# Timer_UNO.net
KiCad netlist of a schematic drawn in EAGLE
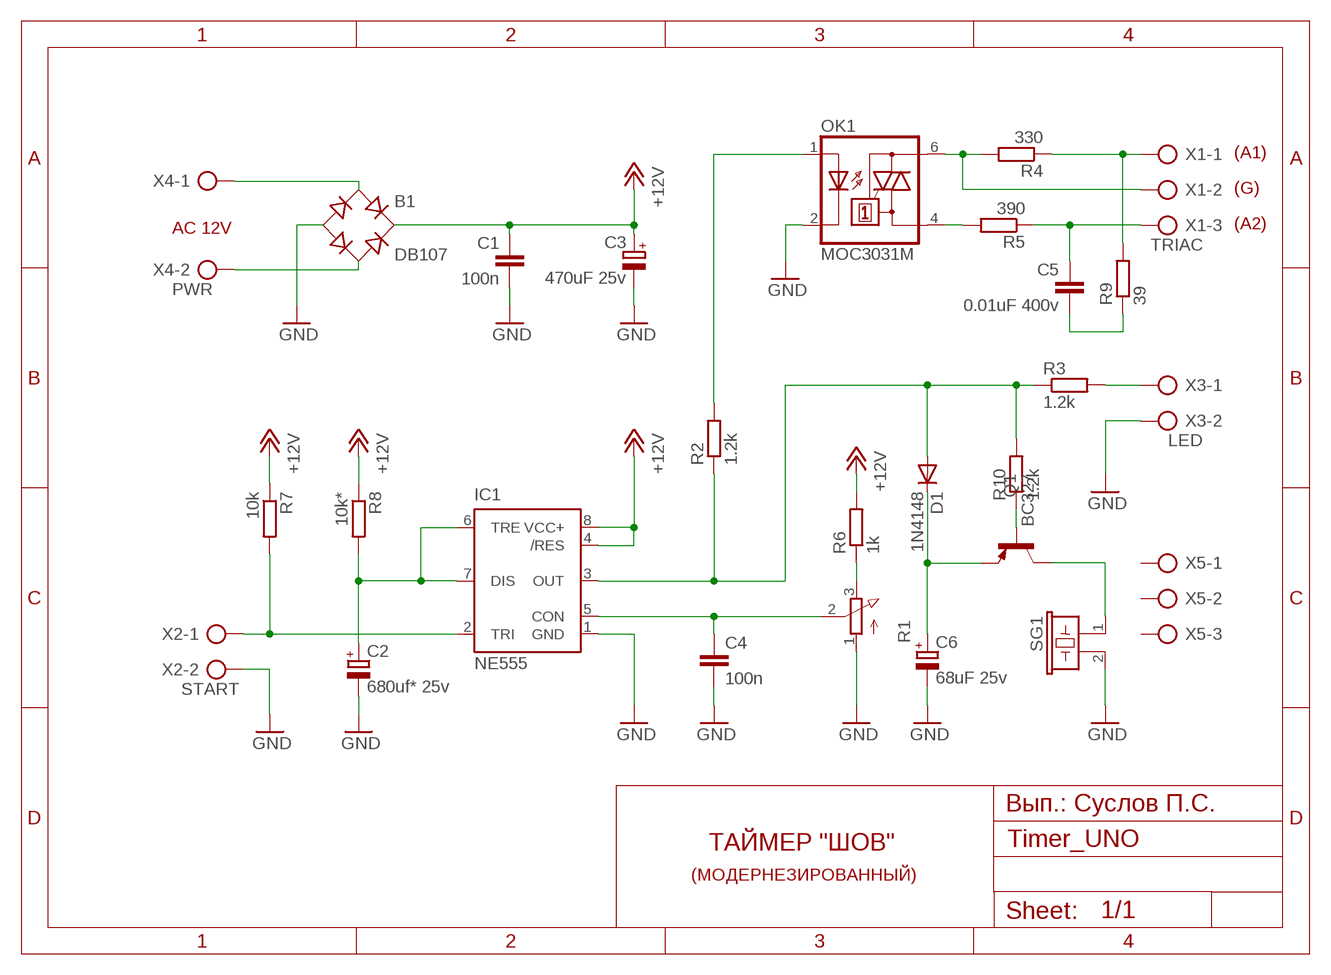
[diagram p0: schematic, sheet 1]

(export (version "E")
  (design (tool "Eeschema 10.0.6"))
  (components
    (comp (ref "B1")
      (value "DB107")
      (footprint "eagle-import:DB")
      (libsource (lib "eagle-import") (part "DB?GDB107"))
    )
    (comp (ref "C1")
      (value "100n")
      (footprint "eagle-import:C025-030X050")
      (libsource (lib "eagle-import") (part "C-EU025-030X050"))
    )
    (comp (ref "C2")
      (value "680uf* 25v")
      (footprint "eagle-import:E3,5-10")
      (libsource (lib "eagle-import") (part "CPOL-EUE3.5-10"))
    )
    (comp (ref "C3")
      (value "470uF 25v")
      (footprint "eagle-import:E3,5-8")
      (libsource (lib "eagle-import") (part "CPOL-EUE3.5-8"))
    )
    (comp (ref "C4")
      (value "100n")
      (footprint "eagle-import:C025-030X050")
      (libsource (lib "eagle-import") (part "C-EU025-030X050"))
    )
    (comp (ref "C5")
      (value "0.01uF 400v")
      (footprint "eagle-import:C075-063X106")
      (libsource (lib "eagle-import") (part "C-EU075-063X106"))
    )
    (comp (ref "C6")
      (value "68uF 25v")
      (footprint "eagle-import:E3,5-8")
      (libsource (lib "eagle-import") (part "CPOL-EUE3.5-8"))
    )
    (comp (ref "D1")
      (value "1N4148")
      (footprint "eagle-import:DO35-7")
      (libsource (lib "eagle-import") (part "1N4148DO35-7"))
    )
    (comp (ref "IC1")
      (value "NE555")
      (footprint "eagle-import:DIL-08")
      (fields (field (name "MF") "Arrow Electronics") (field (name "MPN") "NE555N"))
      (libsource (lib "eagle-import") (part "NE555"))
    )
    (comp (ref "OK1")
      (value "MOC3031M")
      (footprint "eagle-import:DIL06")
      (fields (field (name "MF") "FAIRCHILD SEMICONDUCTOR"))
      (libsource (lib "eagle-import") (part "MOC3031M"))
    )
    (comp (ref "Q1")
      (value "BC327")
      (footprint "eagle-import:TO92-EBC")
      (libsource (lib "eagle-import") (part "BC327"))
    )
    (comp (ref "R1")
      (value "3RP/1610N")
      (footprint "eagle-import:3RP_1610N")
      (libsource (lib "eagle-import") (part "3RP/1610N"))
    )
    (comp (ref "R2")
      (value "1.2k")
      (footprint "eagle-import:0207_10")
      (libsource (lib "eagle-import") (part "R-EU_0207/10"))
    )
    (comp (ref "R3")
      (value "1.2k")
      (footprint "eagle-import:0207_10")
      (libsource (lib "eagle-import") (part "R-EU_0207/10"))
    )
    (comp (ref "R4")
      (value "330")
      (footprint "eagle-import:0207_10")
      (libsource (lib "eagle-import") (part "R-EU_0207/10"))
    )
    (comp (ref "R5")
      (value "390")
      (footprint "eagle-import:0207_10")
      (libsource (lib "eagle-import") (part "R-EU_0207/10"))
    )
    (comp (ref "R6")
      (value "1k")
      (footprint "eagle-import:0207_10")
      (libsource (lib "eagle-import") (part "R-EU_0207/10"))
    )
    (comp (ref "R7")
      (value "10k")
      (footprint "eagle-import:0207_10")
      (libsource (lib "eagle-import") (part "R-EU_0207/10"))
    )
    (comp (ref "R8")
      (value "10k*")
      (footprint "eagle-import:0207_10")
      (libsource (lib "eagle-import") (part "R-EU_0207/10"))
    )
    (comp (ref "R9")
      (value "39")
      (footprint "eagle-import:0411_12")
      (libsource (lib "eagle-import") (part "R-EU_0411/12"))
    )
    (comp (ref "R10")
      (value "1.2k")
      (footprint "eagle-import:0207_10")
      (libsource (lib "eagle-import") (part "R-EU_0207/10"))
    )
    (comp (ref "SG1")
      (value "EFBAA40D101")
      (footprint "eagle-import:EFBAA40D101")
      (libsource (lib "eagle-import") (part "EFB?AA40D101"))
    )
    (comp (ref "X1")
      (value "TRIAC")
      (footprint "eagle-import:AK500_3")
      (libsource (lib "eagle-import") (part "AK500/3"))
    )
    (comp (ref "X2")
      (value "START")
      (footprint "eagle-import:AK500_2")
      (libsource (lib "eagle-import") (part "AK500/2"))
    )
    (comp (ref "X3")
      (value "LED")
      (footprint "eagle-import:AK500_2")
      (libsource (lib "eagle-import") (part "AK500/2"))
    )
    (comp (ref "X4")
      (value "PWR")
      (footprint "eagle-import:AK500_2")
      (libsource (lib "eagle-import") (part "AK500/2"))
    )
    (comp (ref "X5")
      (value "AK500/3")
      (footprint "eagle-import:AK500_3")
      (libsource (lib "eagle-import") (part "AK500/3"))
    )
  )
  (nets
    (net (code "1") (name "+12V") (class "Default")
      (node (ref "B1") (pin "+") (pinfunction "+_+") (pintype "passive"))
      (node (ref "C1") (pin "1") (pinfunction "1_1") (pintype "passive"))
      (node (ref "C3") (pin "+") (pinfunction "+_+") (pintype "passive"))
      (node (ref "IC1") (pin "4") (pinfunction "/RES_4") (pintype "input"))
      (node (ref "IC1") (pin "8") (pinfunction "VCC+_8") (pintype "power_in"))
      (node (ref "R6") (pin "2") (pinfunction "2_2") (pintype "passive"))
      (node (ref "R7") (pin "1") (pinfunction "1_1") (pintype "passive"))
      (node (ref "R8") (pin "1") (pinfunction "1_1") (pintype "passive"))
    )
    (net (code "2") (name "GND") (class "Default")
      (node (ref "B1") (pin "-") (pinfunction "-_-") (pintype "passive"))
      (node (ref "C1") (pin "2") (pinfunction "2_2") (pintype "passive"))
      (node (ref "C2") (pin "-") (pinfunction "-_-") (pintype "passive"))
      (node (ref "C3") (pin "-") (pinfunction "-_-") (pintype "passive"))
      (node (ref "C4") (pin "2") (pinfunction "2_2") (pintype "passive"))
      (node (ref "C6") (pin "-") (pinfunction "-_-") (pintype "passive"))
      (node (ref "IC1") (pin "1") (pinfunction "GND_1") (pintype "power_in"))
      (node (ref "OK1") (pin "2") (pinfunction "C_2") (pintype "passive"))
      (node (ref "R1") (pin "1") (pinfunction "A_1") (pintype "passive"))
      (node (ref "SG1") (pin "2") (pinfunction "2_2") (pintype "passive"))
      (node (ref "X2") (pin "2") (pinfunction "KL_2") (pintype "passive"))
      (node (ref "X3") (pin "2") (pinfunction "KL_2") (pintype "passive"))
    )
    (net (code "3") (name "Net-(C5-Pad2)") (class "Default")
      (node (ref "C5") (pin "2") (pinfunction "2_2") (pintype "passive"))
      (node (ref "R9") (pin "1") (pinfunction "1_1") (pintype "passive"))
    )
    (net (code "4") (name "Net-(C6-Pad+)") (class "Default")
      (node (ref "C6") (pin "+") (pinfunction "+_+") (pintype "passive"))
      (node (ref "D1") (pin "C") (pinfunction "C_C") (pintype "passive"))
      (node (ref "Q1") (pin "E") (pinfunction "E_E") (pintype "passive"))
    )
    (net (code "5") (name "Net-(IC1-CON)") (class "Default")
      (node (ref "C4") (pin "1") (pinfunction "1_1") (pintype "passive"))
      (node (ref "IC1") (pin "5") (pinfunction "CON_5") (pintype "input"))
      (node (ref "R1") (pin "2") (pinfunction "S_2") (pintype "passive"))
    )
    (net (code "6") (name "Net-(IC1-DIS)") (class "Default")
      (node (ref "C2") (pin "+") (pinfunction "+_+") (pintype "passive"))
      (node (ref "IC1") (pin "6") (pinfunction "TRE_6") (pintype "input"))
      (node (ref "IC1") (pin "7") (pinfunction "DIS_7") (pintype "input"))
      (node (ref "R8") (pin "2") (pinfunction "2_2") (pintype "passive"))
    )
    (net (code "7") (name "Net-(IC1-OUT)") (class "Default")
      (node (ref "D1") (pin "A") (pinfunction "A_A") (pintype "passive"))
      (node (ref "IC1") (pin "3") (pinfunction "OUT_3") (pintype "output"))
      (node (ref "R10") (pin "2") (pinfunction "2_2") (pintype "passive"))
      (node (ref "R2") (pin "1") (pinfunction "1_1") (pintype "passive"))
      (node (ref "R3") (pin "1") (pinfunction "1_1") (pintype "passive"))
    )
    (net (code "8") (name "Net-(IC1-TRI)") (class "Default")
      (node (ref "IC1") (pin "2") (pinfunction "TRI_2") (pintype "input"))
      (node (ref "R7") (pin "2") (pinfunction "2_2") (pintype "passive"))
      (node (ref "X2") (pin "1") (pinfunction "KL_1") (pintype "passive"))
    )
    (net (code "9") (name "Net-(OK1-A)") (class "Default")
      (node (ref "OK1") (pin "1") (pinfunction "A_1") (pintype "passive"))
      (node (ref "R2") (pin "2") (pinfunction "2_2") (pintype "passive"))
    )
    (net (code "10") (name "Net-(OK1-A1)") (class "Default")
      (node (ref "OK1") (pin "4") (pinfunction "A1_4") (pintype "passive"))
      (node (ref "R5") (pin "2") (pinfunction "2_2") (pintype "passive"))
    )
    (net (code "11") (name "Net-(OK1-A2)") (class "Default")
      (node (ref "OK1") (pin "6") (pinfunction "A2_6") (pintype "passive"))
      (node (ref "R4") (pin "2") (pinfunction "2_2") (pintype "passive"))
      (node (ref "X1") (pin "2") (pinfunction "KL_2") (pintype "passive"))
    )
    (net (code "12") (name "Net-(Q1-PadB)") (class "Default")
      (node (ref "Q1") (pin "B") (pinfunction "B_B") (pintype "passive"))
      (node (ref "R10") (pin "1") (pinfunction "1_1") (pintype "passive"))
    )
    (net (code "13") (name "Net-(Q1-PadC)") (class "Default")
      (node (ref "Q1") (pin "C") (pinfunction "C_C") (pintype "passive"))
      (node (ref "SG1") (pin "1") (pinfunction "1_1") (pintype "passive"))
    )
    (net (code "14") (name "Net-(R1-E)") (class "Default")
      (node (ref "R1") (pin "3") (pinfunction "E_3") (pintype "passive"))
      (node (ref "R6") (pin "1") (pinfunction "1_1") (pintype "passive"))
    )
    (net (code "15") (name "Net-(X1A-KL)") (class "Default")
      (node (ref "R4") (pin "1") (pinfunction "1_1") (pintype "passive"))
      (node (ref "R9") (pin "2") (pinfunction "2_2") (pintype "passive"))
      (node (ref "X1") (pin "1") (pinfunction "KL_1") (pintype "passive"))
    )
    (net (code "16") (name "Net-(X1C-KL)") (class "Default")
      (node (ref "C5") (pin "1") (pinfunction "1_1") (pintype "passive"))
      (node (ref "R5") (pin "1") (pinfunction "1_1") (pintype "passive"))
      (node (ref "X1") (pin "3") (pinfunction "KL_3") (pintype "passive"))
    )
    (net (code "17") (name "Net-(X3A-KL)") (class "Default")
      (node (ref "R3") (pin "2") (pinfunction "2_2") (pintype "passive"))
      (node (ref "X3") (pin "1") (pinfunction "KL_1") (pintype "passive"))
    )
    (net (code "18") (name "Net-(X4A-KL)") (class "Default")
      (node (ref "B1") (pin "AC1") (pinfunction "AC1_AC1") (pintype "passive"))
      (node (ref "X4") (pin "1") (pinfunction "KL_1") (pintype "passive"))
    )
    (net (code "19") (name "Net-(X4B-KL)") (class "Default")
      (node (ref "B1") (pin "AC2") (pinfunction "AC2_AC2") (pintype "passive"))
      (node (ref "X4") (pin "2") (pinfunction "KL_2") (pintype "passive"))
    )
    (net (code "20") (name "unconnected-(X5A-KL-Pad1)") (class "Default")
      (node (ref "X5") (pin "1") (pinfunction "KL_1") (pintype "passive"))
    )
    (net (code "21") (name "unconnected-(X5B-KL-Pad2)") (class "Default")
      (node (ref "X5") (pin "2") (pinfunction "KL_2") (pintype "passive"))
    )
    (net (code "22") (name "unconnected-(X5C-KL-Pad3)") (class "Default")
      (node (ref "X5") (pin "3") (pinfunction "KL_3") (pintype "passive"))
    )
  )
)
